# GPIO.net
KiCad netlist of a schematic drawn in Altium Designer
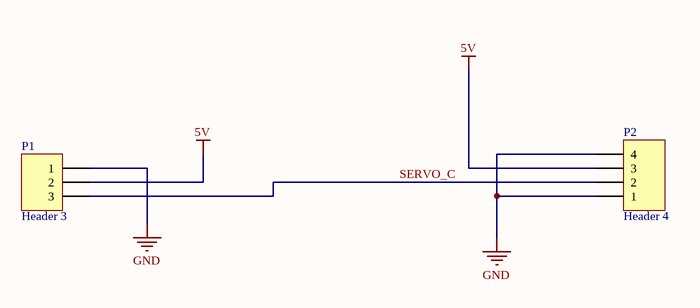
[diagram p0: GPIO.SchDoc]

(export (version "E")
  (design (tool "Eeschema 10.0.6"))
  (components
    (comp (ref "P1")
      (value "Header 3")
      (footprint "HDR1X3")
      (description "Header, 3-Pin")
      (fields (field (name "PUBLISHER") "Altium Limited"))
      (libsource (lib "Miscellaneous Connectors") (part "Header 3"))
    )
    (comp (ref "P2")
      (value "Header 4")
      (footprint "CONfLAT")
      (description "Header, 4-Pin")
      (fields (field (name "PUBLISHER") "Altium Limited"))
      (libsource (lib "Miscellaneous Connectors") (part "Header 4"))
    )
  )
  (nets
    (net (code "1") (name "/SERVO_C") (class "Default")
      (node (ref "P1") (pin "3") (pinfunction "3_3") (pintype "passive"))
      (node (ref "P2") (pin "2") (pinfunction "2_2") (pintype "passive"))
    )
    (net (code "2") (name "5V") (class "Default")
      (node (ref "P1") (pin "2") (pinfunction "2_2") (pintype "passive"))
      (node (ref "P2") (pin "3") (pinfunction "3_3") (pintype "passive"))
    )
    (net (code "3") (name "GND") (class "Default")
      (node (ref "P1") (pin "1") (pinfunction "1_1") (pintype "passive"))
      (node (ref "P2") (pin "1") (pinfunction "1_1") (pintype "passive"))
      (node (ref "P2") (pin "4") (pinfunction "4_4") (pintype "passive"))
    )
  )
)
